# Sheet1.net
KiCad netlist of a schematic drawn in Altium Designer
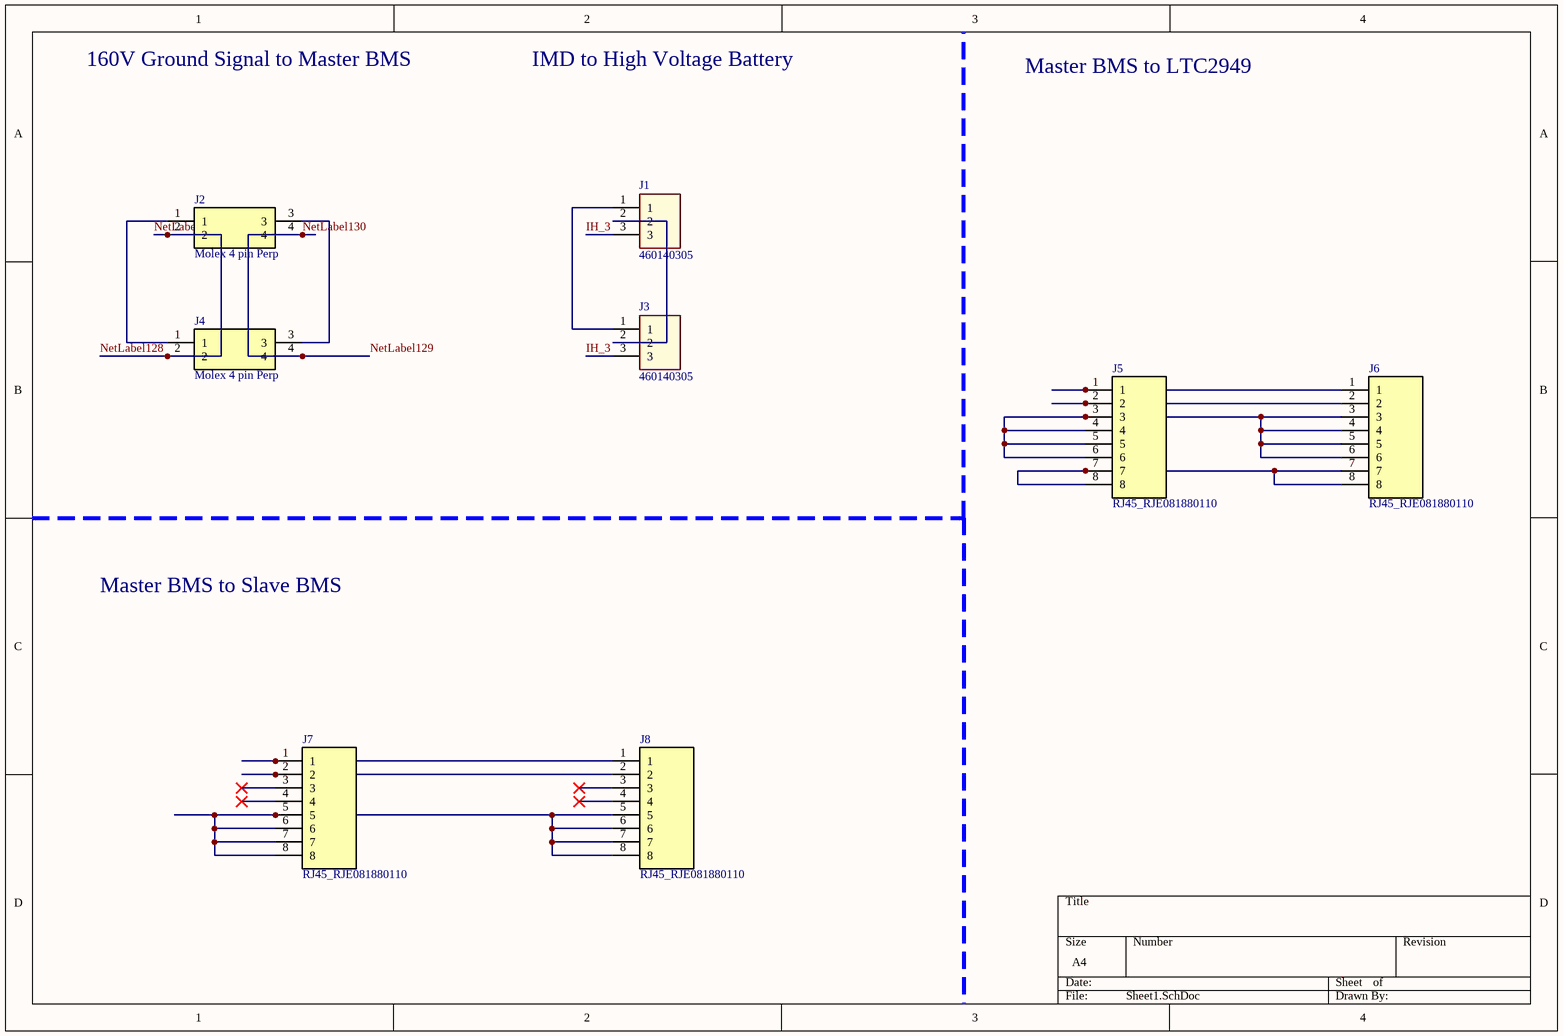
[diagram p0: Sheet1.SchDoc]

(export (version "E")
  (design (tool "Eeschema 10.0.6"))
  (components
    (comp (ref "J1")
      (value "460140305")
      (footprint "MOLEX_460140305_3pin header")
      (libsource (lib "GeneralConnectors") (part "460140305"))
    )
    (comp (ref "J2")
      (value "Molex 4 pin Perp")
      (footprint "MOLEX_462071004")
      (description "Connector Header Through Hole 4 position 0.165in (4.20mm)")
      (fields (field (name "MP") "462071004"))
      (libsource (lib "GeneralConnectors") (part "Molex 4 pin Perp"))
    )
    (comp (ref "J3")
      (value "460140305")
      (footprint "MOLEX_460140305_3pin header")
      (libsource (lib "GeneralConnectors") (part "460140305"))
    )
    (comp (ref "J4")
      (value "Molex 4 pin Perp")
      (footprint "MOLEX_462071004")
      (description "Connector Header Through Hole 4 position 0.165in (4.20mm)")
      (fields (field (name "MP") "462071004"))
      (libsource (lib "GeneralConnectors") (part "Molex 4 pin Perp"))
    )
    (comp (ref "J5")
      (value "RJ45_RJE081880110")
      (footprint "RJ45_RJE081880110")
      (description "RJ45 Modular Jack - Verticals, Input Output Connectors 8P8C, Without Shield.")
      (fields (field (name "MF") "Amphenol ICC (Commercial Products)") (field (name "MP") "RJE081880110"))
      (libsource (lib "GeneralConnectors") (part "RJ45_RJE081880110"))
    )
    (comp (ref "J6")
      (value "RJ45_RJE081880110")
      (footprint "RJ45_RJE081880110")
      (description "RJ45 Modular Jack - Verticals, Input Output Connectors 8P8C, Without Shield.")
      (fields (field (name "MF") "Amphenol ICC (Commercial Products)") (field (name "MP") "RJE081880110"))
      (libsource (lib "GeneralConnectors") (part "RJ45_RJE081880110"))
    )
    (comp (ref "J7")
      (value "RJ45_RJE081880110")
      (footprint "RJ45_RJE081880110")
      (description "RJ45 Modular Jack - Verticals, Input Output Connectors 8P8C, Without Shield.")
      (fields (field (name "MF") "Amphenol ICC (Commercial Products)") (field (name "MP") "RJE081880110"))
      (libsource (lib "GeneralConnectors") (part "RJ45_RJE081880110"))
    )
    (comp (ref "J8")
      (value "RJ45_RJE081880110")
      (footprint "RJ45_RJE081880110")
      (description "RJ45 Modular Jack - Verticals, Input Output Connectors 8P8C, Without Shield.")
      (fields (field (name "MF") "Amphenol ICC (Commercial Products)") (field (name "MP") "RJE081880110"))
      (libsource (lib "GeneralConnectors") (part "RJ45_RJE081880110"))
    )
  )
  (nets
    (net (code "1") (name "/IH_3") (class "Default")
      (node (ref "J1") (pin "3") (pinfunction "3_3") (pintype "passive"))
      (node (ref "J3") (pin "3") (pinfunction "3_3") (pintype "passive"))
    )
    (net (code "2") (name "/NetLabel127") (class "Default")
      (node (ref "J2") (pin "2") (pinfunction "2_2") (pintype "passive"))
      (node (ref "J4") (pin "2") (pinfunction "2_2") (pintype "passive"))
    )
    (net (code "3") (name "/NetLabel129") (class "Default")
      (node (ref "J2") (pin "4") (pinfunction "4_4") (pintype "passive"))
      (node (ref "J4") (pin "4") (pinfunction "4_4") (pintype "passive"))
    )
    (net (code "4") (name "Net-(J1-Pad1)") (class "Default")
      (node (ref "J1") (pin "1") (pinfunction "1_1") (pintype "passive"))
      (node (ref "J3") (pin "1") (pinfunction "1_1") (pintype "passive"))
    )
    (net (code "5") (name "Net-(J1-Pad2)") (class "Default")
      (node (ref "J1") (pin "2") (pinfunction "2_2") (pintype "passive"))
      (node (ref "J3") (pin "2") (pinfunction "2_2") (pintype "passive"))
    )
    (net (code "6") (name "Net-(J2-Pad1)") (class "Default")
      (node (ref "J2") (pin "1") (pinfunction "1_1") (pintype "passive"))
      (node (ref "J4") (pin "1") (pinfunction "1_1") (pintype "passive"))
    )
    (net (code "7") (name "Net-(J2-Pad3)") (class "Default")
      (node (ref "J2") (pin "3") (pinfunction "3_3") (pintype "passive"))
      (node (ref "J4") (pin "3") (pinfunction "3_3") (pintype "passive"))
    )
    (net (code "8") (name "Net-(J5-Pad1)") (class "Default")
      (node (ref "J5") (pin "1") (pinfunction "1_1") (pintype "passive"))
      (node (ref "J6") (pin "1") (pinfunction "1_1") (pintype "passive"))
    )
    (net (code "9") (name "Net-(J5-Pad2)") (class "Default")
      (node (ref "J5") (pin "2") (pinfunction "2_2") (pintype "passive"))
      (node (ref "J6") (pin "2") (pinfunction "2_2") (pintype "passive"))
    )
    (net (code "10") (name "Net-(J5-Pad3)") (class "Default")
      (node (ref "J5") (pin "3") (pinfunction "3_3") (pintype "passive"))
      (node (ref "J5") (pin "4") (pinfunction "4_4") (pintype "passive"))
      (node (ref "J5") (pin "5") (pinfunction "5_5") (pintype "passive"))
      (node (ref "J5") (pin "6") (pinfunction "6_6") (pintype "passive"))
      (node (ref "J6") (pin "3") (pinfunction "3_3") (pintype "passive"))
      (node (ref "J6") (pin "4") (pinfunction "4_4") (pintype "passive"))
      (node (ref "J6") (pin "5") (pinfunction "5_5") (pintype "passive"))
      (node (ref "J6") (pin "6") (pinfunction "6_6") (pintype "passive"))
    )
    (net (code "11") (name "Net-(J5-Pad7)") (class "Default")
      (node (ref "J5") (pin "7") (pinfunction "7_7") (pintype "passive"))
      (node (ref "J5") (pin "8") (pinfunction "8_8") (pintype "passive"))
      (node (ref "J6") (pin "7") (pinfunction "7_7") (pintype "passive"))
      (node (ref "J6") (pin "8") (pinfunction "8_8") (pintype "passive"))
    )
    (net (code "12") (name "Net-(J7-Pad1)") (class "Default")
      (node (ref "J7") (pin "1") (pinfunction "1_1") (pintype "passive"))
      (node (ref "J8") (pin "1") (pinfunction "1_1") (pintype "passive"))
    )
    (net (code "13") (name "Net-(J7-Pad2)") (class "Default")
      (node (ref "J7") (pin "2") (pinfunction "2_2") (pintype "passive"))
      (node (ref "J8") (pin "2") (pinfunction "2_2") (pintype "passive"))
    )
    (net (code "14") (name "Net-(J7-Pad5)") (class "Default")
      (node (ref "J7") (pin "5") (pinfunction "5_5") (pintype "passive"))
      (node (ref "J7") (pin "6") (pinfunction "6_6") (pintype "passive"))
      (node (ref "J7") (pin "7") (pinfunction "7_7") (pintype "passive"))
      (node (ref "J7") (pin "8") (pinfunction "8_8") (pintype "passive"))
      (node (ref "J8") (pin "5") (pinfunction "5_5") (pintype "passive"))
      (node (ref "J8") (pin "6") (pinfunction "6_6") (pintype "passive"))
      (node (ref "J8") (pin "7") (pinfunction "7_7") (pintype "passive"))
      (node (ref "J8") (pin "8") (pinfunction "8_8") (pintype "passive"))
    )
    (net (code "15") (name "unconnected-(J7-Pad3)") (class "Default")
      (node (ref "J7") (pin "3") (pinfunction "3_3") (pintype "passive+no_connect"))
    )
    (net (code "16") (name "unconnected-(J7-Pad4)") (class "Default")
      (node (ref "J7") (pin "4") (pinfunction "4_4") (pintype "passive+no_connect"))
    )
    (net (code "17") (name "unconnected-(J8-Pad3)") (class "Default")
      (node (ref "J8") (pin "3") (pinfunction "3_3") (pintype "passive+no_connect"))
    )
    (net (code "18") (name "unconnected-(J8-Pad4)") (class "Default")
      (node (ref "J8") (pin "4") (pinfunction "4_4") (pintype "passive+no_connect"))
    )
  )
)
